# 28P1.net
KiCad netlist of a schematic drawn in Altium Designer
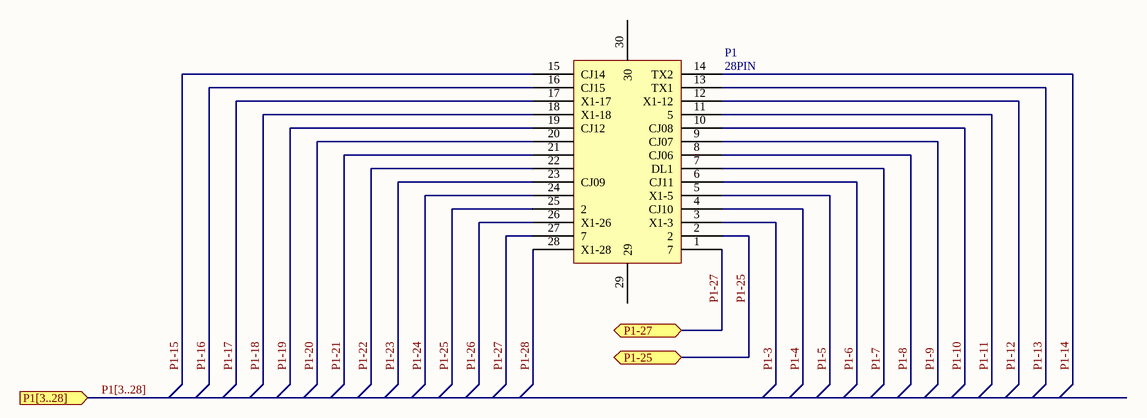
[diagram p0: 28P1.SchDoc]

(export (version "E")
  (design (tool "Eeschema 10.0.6"))
  (components
    (comp (ref "P1") (value "28PIN") (footprint "2*14") (libsource (lib "28PIN") (part "Component_1")))
  )
  (nets
    (net (code "27") (name "/P1-3") (class "Default")
      (node (ref "P1") (pin "3") (pinfunction "X1-3_3") (pintype "passive"))
    )
    (net (code "28") (name "/P1-4") (class "Default")
      (node (ref "P1") (pin "4") (pinfunction "CJ10_4") (pintype "passive"))
    )
    (net (code "29") (name "/P1-5") (class "Default")
      (node (ref "P1") (pin "5") (pinfunction "X1-5_5") (pintype "passive"))
    )
    (net (code "30") (name "/P1-6") (class "Default")
      (node (ref "P1") (pin "6") (pinfunction "CJ11_6") (pintype "passive"))
    )
    (net (code "31") (name "/P1-7") (class "Default")
      (node (ref "P1") (pin "7") (pinfunction "DL1_7") (pintype "passive"))
    )
    (net (code "32") (name "/P1-8") (class "Default")
      (node (ref "P1") (pin "8") (pinfunction "CJ06_8") (pintype "passive"))
    )
    (net (code "33") (name "/P1-9") (class "Default")
      (node (ref "P1") (pin "9") (pinfunction "CJ07_9") (pintype "passive"))
    )
    (net (code "34") (name "/P1-10") (class "Default")
      (node (ref "P1") (pin "10") (pinfunction "CJ08_10") (pintype "passive"))
    )
    (net (code "35") (name "/P1-11") (class "Default")
      (node (ref "P1") (pin "11") (pinfunction "5_11") (pintype "passive"))
    )
    (net (code "36") (name "/P1-12") (class "Default")
      (node (ref "P1") (pin "12") (pinfunction "X1-12_12") (pintype "passive"))
    )
    (net (code "37") (name "/P1-13") (class "Default")
      (node (ref "P1") (pin "13") (pinfunction "TX1_13") (pintype "passive"))
    )
    (net (code "38") (name "/P1-14") (class "Default")
      (node (ref "P1") (pin "14") (pinfunction "TX2_14") (pintype "passive"))
    )
    (net (code "39") (name "/P1-15") (class "Default")
      (node (ref "P1") (pin "15") (pinfunction "CJ14_15") (pintype "passive"))
    )
    (net (code "40") (name "/P1-16") (class "Default")
      (node (ref "P1") (pin "16") (pinfunction "CJ15_16") (pintype "passive"))
    )
    (net (code "41") (name "/P1-17") (class "Default")
      (node (ref "P1") (pin "17") (pinfunction "X1-17_17") (pintype "passive"))
    )
    (net (code "42") (name "/P1-18") (class "Default")
      (node (ref "P1") (pin "18") (pinfunction "X1-18_18") (pintype "passive"))
    )
    (net (code "43") (name "/P1-19") (class "Default")
      (node (ref "P1") (pin "19") (pinfunction "CJ12_19") (pintype "passive"))
    )
    (net (code "44") (name "/P1-20") (class "Default")
      (node (ref "P1") (pin "20") (pinfunction "20_20") (pintype "passive"))
    )
    (net (code "45") (name "/P1-21") (class "Default")
      (node (ref "P1") (pin "21") (pinfunction "21_21") (pintype "passive"))
    )
    (net (code "46") (name "/P1-22") (class "Default")
      (node (ref "P1") (pin "22") (pinfunction "22_22") (pintype "passive"))
    )
    (net (code "47") (name "/P1-23") (class "Default")
      (node (ref "P1") (pin "23") (pinfunction "CJ09_23") (pintype "passive"))
    )
    (net (code "48") (name "/P1-24") (class "Default")
      (node (ref "P1") (pin "24") (pinfunction "24_24") (pintype "passive"))
    )
    (net (code "49") (name "/P1-25") (class "Default")
      (node (ref "P1") (pin "2") (pinfunction "2_2") (pintype "passive"))
      (node (ref "P1") (pin "25") (pinfunction "2_25") (pintype "passive"))
    )
    (net (code "50") (name "/P1-26") (class "Default")
      (node (ref "P1") (pin "26") (pinfunction "X1-26_26") (pintype "passive"))
    )
    (net (code "51") (name "/P1-27") (class "Default")
      (node (ref "P1") (pin "1") (pinfunction "7_1") (pintype "passive"))
      (node (ref "P1") (pin "27") (pinfunction "7_27") (pintype "passive"))
    )
    (net (code "52") (name "/P1-28") (class "Default")
      (node (ref "P1") (pin "28") (pinfunction "X1-28_28") (pintype "passive"))
    )
    (net (code "54") (name "unconnected-(P1-Pad29)") (class "Default")
      (node (ref "P1") (pin "29") (pinfunction "29_29") (pintype "passive"))
    )
    (net (code "55") (name "unconnected-(P1-Pad30)") (class "Default")
      (node (ref "P1") (pin "30") (pinfunction "30_30") (pintype "passive"))
    )
  )
)
